# bl_dora2.net
KiCad netlist of a schematic drawn in EAGLE
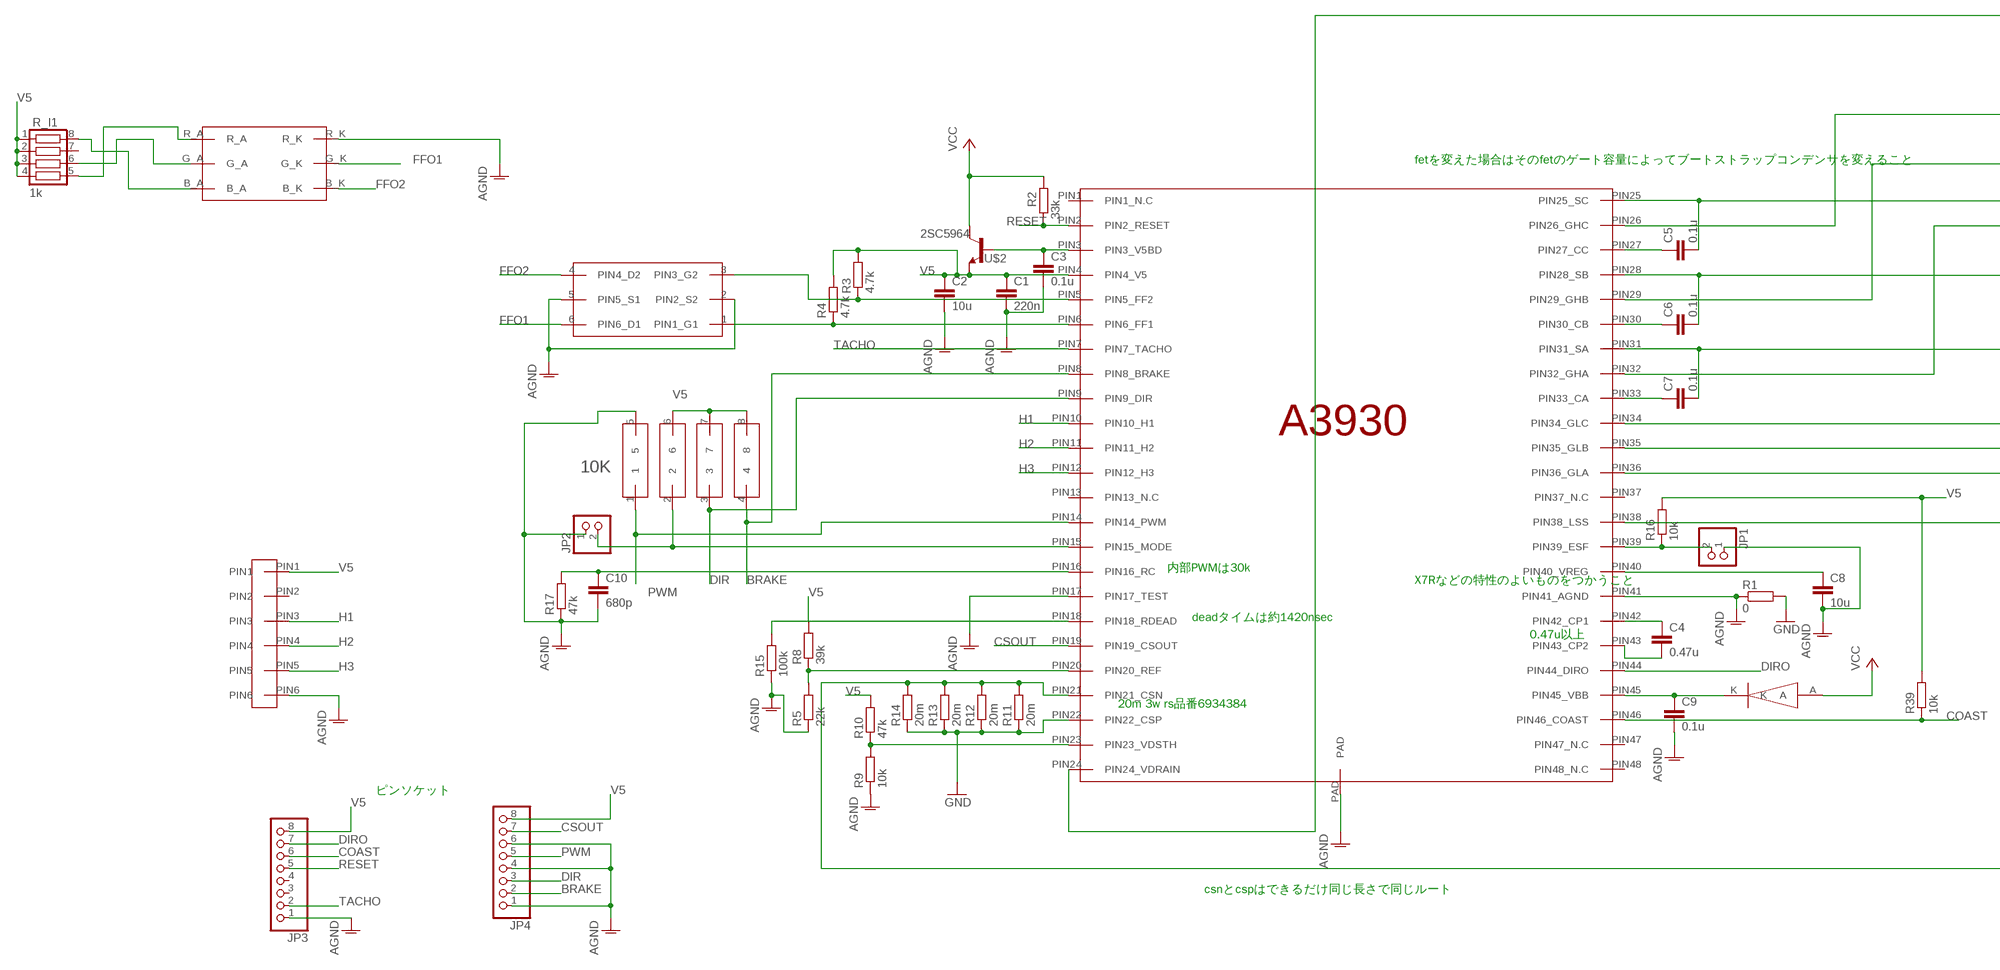
[diagram p0: schematic, sheet 1, part 1 of 2]
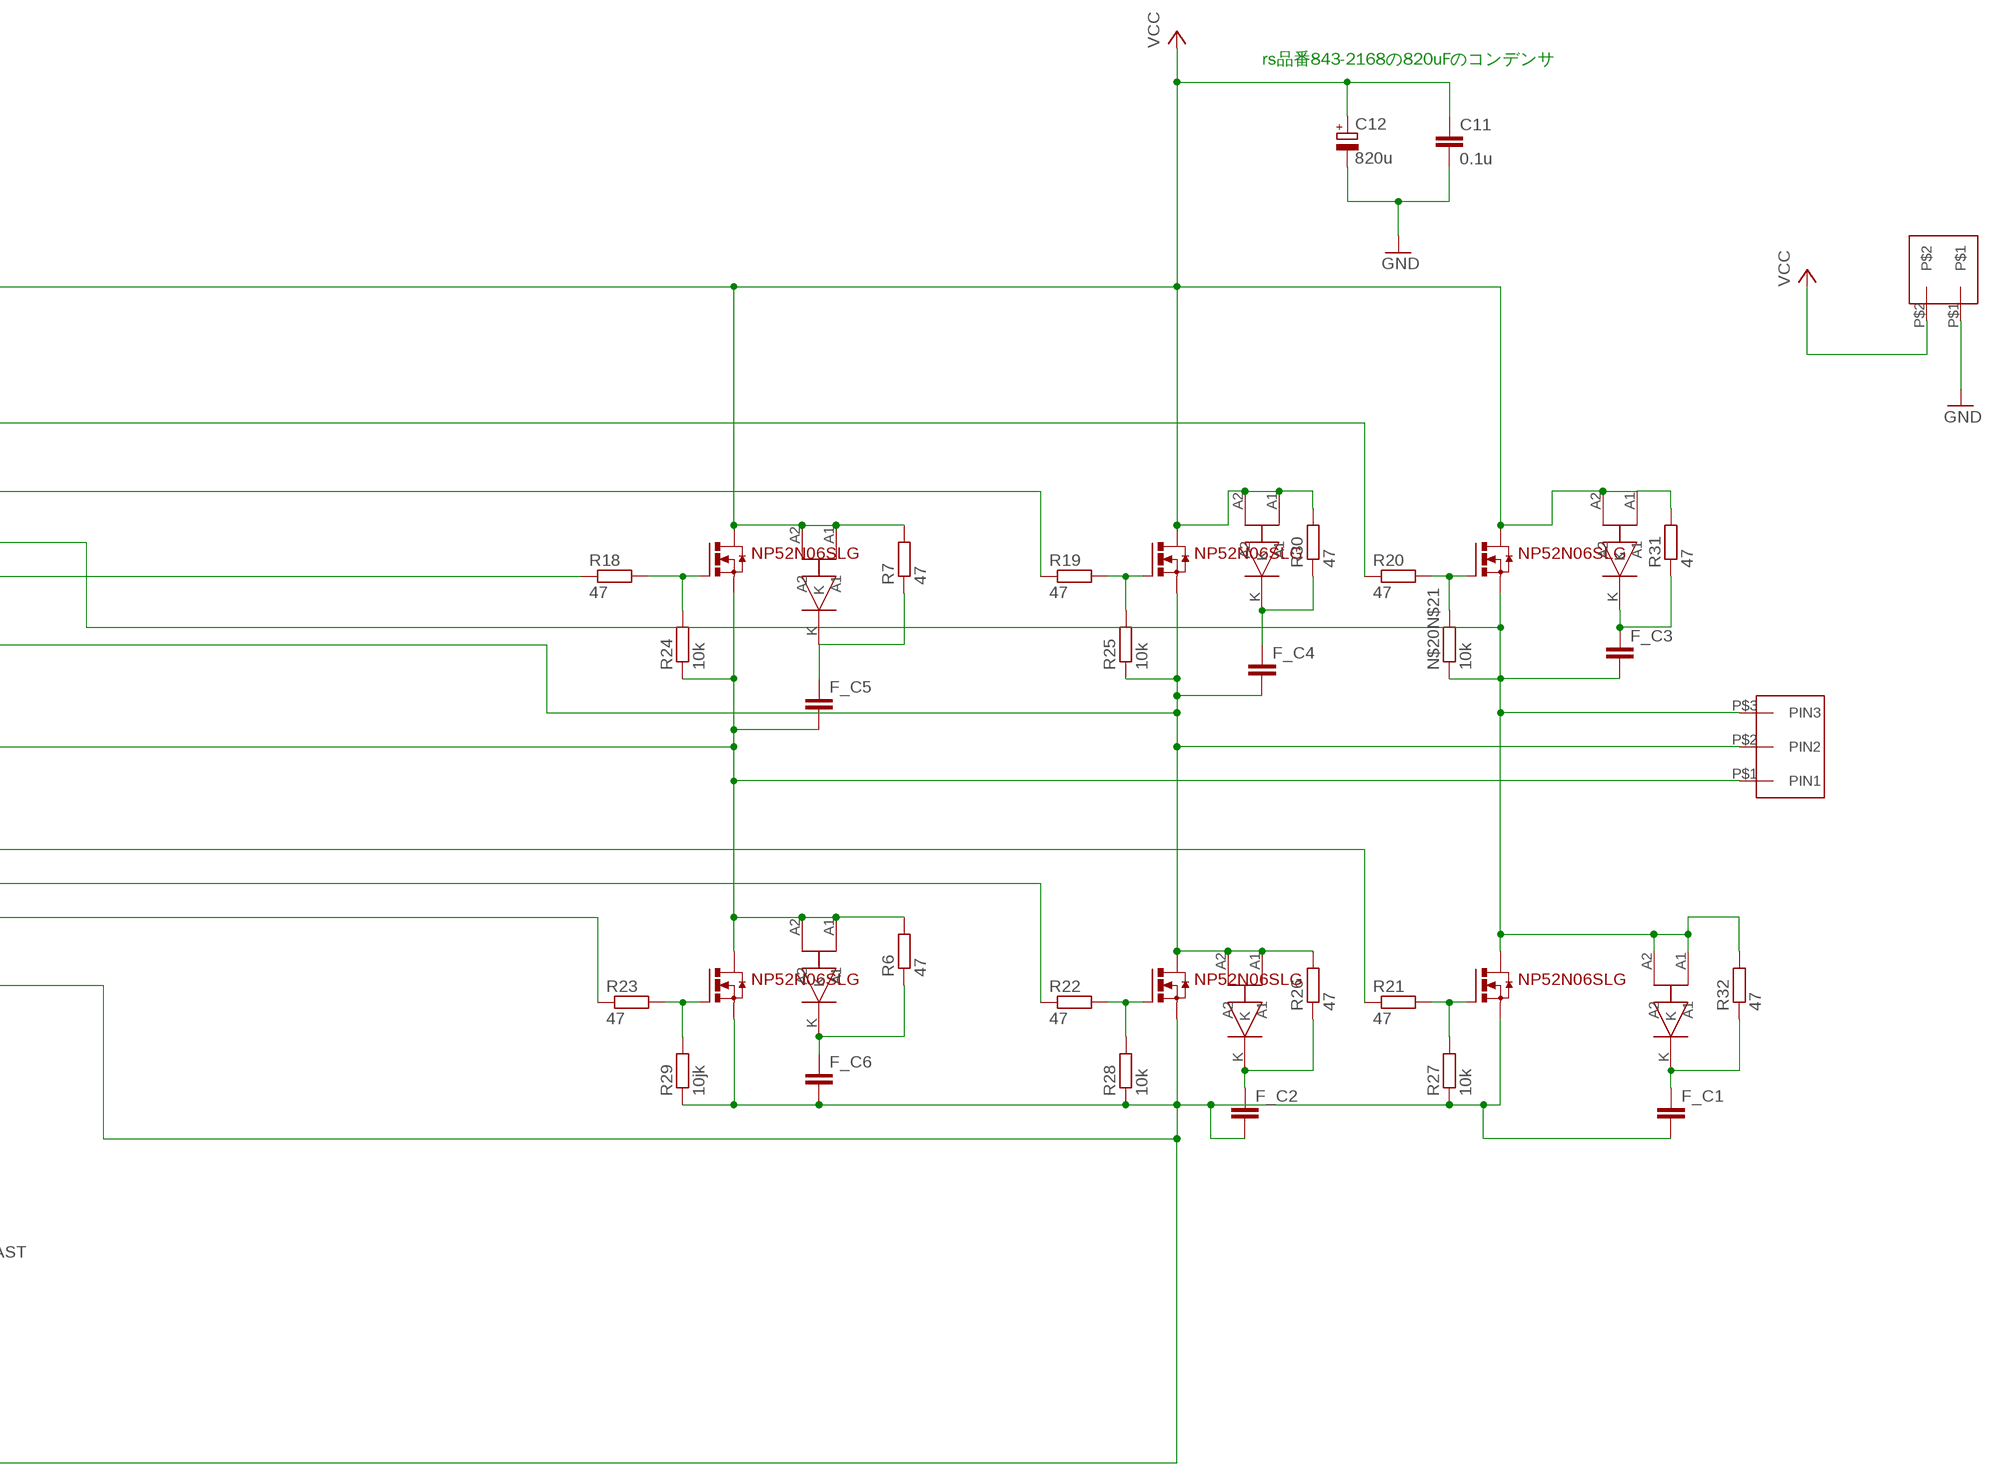
[diagram p1: schematic, sheet 1, part 2 of 2]

(export (version "E")
  (design (tool "Eeschema 10.0.6"))
  (components
    (comp (ref "C1")
      (value "220n")
      (footprint "eagle-import:C2012")
      (libsource (lib "eagle-import") (part "C-EUC2012"))
    )
    (comp (ref "C2")
      (value "10u")
      (footprint "eagle-import:C2012")
      (libsource (lib "eagle-import") (part "C-EUC2012"))
    )
    (comp (ref "C3")
      (value "0.1u")
      (footprint "eagle-import:C2012")
      (libsource (lib "eagle-import") (part "C-EUC2012"))
    )
    (comp (ref "C4")
      (value "0.47u")
      (footprint "eagle-import:C2012")
      (libsource (lib "eagle-import") (part "C-EUC2012"))
    )
    (comp (ref "C5")
      (value "0.1u")
      (footprint "eagle-import:C2012")
      (libsource (lib "eagle-import") (part "C-EUC2012"))
    )
    (comp (ref "C6")
      (value "0.1u")
      (footprint "eagle-import:C2012")
      (libsource (lib "eagle-import") (part "C-EUC2012"))
    )
    (comp (ref "C7")
      (value "0.1u")
      (footprint "eagle-import:C2012")
      (libsource (lib "eagle-import") (part "C-EUC2012"))
    )
    (comp (ref "C8")
      (value "10u")
      (footprint "eagle-import:C2012")
      (libsource (lib "eagle-import") (part "C-EUC2012"))
    )
    (comp (ref "C9")
      (value "0.1u")
      (footprint "eagle-import:C2012")
      (libsource (lib "eagle-import") (part "C-EUC2012"))
    )
    (comp (ref "C10")
      (value "680p")
      (footprint "eagle-import:C2012")
      (libsource (lib "eagle-import") (part "C-EUC2012"))
    )
    (comp (ref "C11")
      (value "0.1u")
      (footprint "eagle-import:C2012")
      (libsource (lib "eagle-import") (part "C-EUC2012"))
    )
    (comp (ref "C12")
      (value "820u")
      (footprint "eagle-import:153CLV-1012")
      (libsource (lib "eagle-import") (part "CPOL-EU153CLV-1012"))
    )
    (comp (ref "F_C1")
      (value "FIL_CAPA")
      (footprint "eagle-import:FIL_CAPA")
      (libsource (lib "eagle-import") (part "FIL_CAPA"))
    )
    (comp (ref "F_C2")
      (value "FIL_CAPA")
      (footprint "eagle-import:FIL_CAPA")
      (libsource (lib "eagle-import") (part "FIL_CAPA"))
    )
    (comp (ref "F_C3")
      (value "FIL_CAPA")
      (footprint "eagle-import:FIL_CAPA")
      (libsource (lib "eagle-import") (part "FIL_CAPA"))
    )
    (comp (ref "F_C4")
      (value "FIL_CAPA")
      (footprint "eagle-import:FIL_CAPA")
      (libsource (lib "eagle-import") (part "FIL_CAPA"))
    )
    (comp (ref "F_C5")
      (value "FIL_CAPA")
      (footprint "eagle-import:FIL_CAPA")
      (libsource (lib "eagle-import") (part "FIL_CAPA"))
    )
    (comp (ref "F_C6")
      (value "FIL_CAPA")
      (footprint "eagle-import:FIL_CAPA")
      (libsource (lib "eagle-import") (part "FIL_CAPA"))
    )
    (comp (ref "JP1")
      (value "PINHD-1X2")
      (footprint "eagle-import:1X02")
      (libsource (lib "eagle-import") (part "PINHD-1X2"))
    )
    (comp (ref "JP2")
      (value "PINHD-1X2")
      (footprint "eagle-import:1X02")
      (libsource (lib "eagle-import") (part "PINHD-1X2"))
    )
    (comp (ref "JP3")
      (value "PINHD-1X8")
      (footprint "eagle-import:1X08")
      (libsource (lib "eagle-import") (part "PINHD-1X8"))
    )
    (comp (ref "JP4")
      (value "PINHD-1X8")
      (footprint "eagle-import:1X08")
      (libsource (lib "eagle-import") (part "PINHD-1X8"))
    )
    (comp (ref "N$20N$21")
      (value "10k")
      (footprint "eagle-import:M2012")
      (libsource (lib "eagle-import") (part "R-EU_M2012"))
    )
    (comp (ref "R1")
      (value "0")
      (footprint "eagle-import:M2012")
      (libsource (lib "eagle-import") (part "R-EU_M2012"))
    )
    (comp (ref "R2")
      (value "33k")
      (footprint "eagle-import:M2012")
      (libsource (lib "eagle-import") (part "R-EU_M2012"))
    )
    (comp (ref "R3")
      (value "4.7k")
      (footprint "eagle-import:M2012")
      (libsource (lib "eagle-import") (part "R-EU_M2012"))
    )
    (comp (ref "R4")
      (value "4.7k")
      (footprint "eagle-import:M2012")
      (libsource (lib "eagle-import") (part "R-EU_M2012"))
    )
    (comp (ref "R5")
      (value "22k")
      (footprint "eagle-import:M2012")
      (libsource (lib "eagle-import") (part "R-EU_M2012"))
    )
    (comp (ref "R6")
      (value "47")
      (footprint "eagle-import:R2512")
      (libsource (lib "eagle-import") (part "R-EU_R2512"))
    )
    (comp (ref "R7")
      (value "47")
      (footprint "eagle-import:R2512")
      (libsource (lib "eagle-import") (part "R-EU_R2512"))
    )
    (comp (ref "R8")
      (value "39k")
      (footprint "eagle-import:M2012")
      (libsource (lib "eagle-import") (part "R-EU_M2012"))
    )
    (comp (ref "R9")
      (value "10k")
      (footprint "eagle-import:M2012")
      (libsource (lib "eagle-import") (part "R-EU_M2012"))
    )
    (comp (ref "R10")
      (value "47k")
      (footprint "eagle-import:M2012")
      (libsource (lib "eagle-import") (part "R-EU_M2012"))
    )
    (comp (ref "R11")
      (value "20m")
      (footprint "eagle-import:R2512")
      (libsource (lib "eagle-import") (part "R-EU_R2512"))
    )
    (comp (ref "R12")
      (value "20m")
      (footprint "eagle-import:R2512")
      (libsource (lib "eagle-import") (part "R-EU_R2512"))
    )
    (comp (ref "R13")
      (value "20m")
      (footprint "eagle-import:R2512")
      (libsource (lib "eagle-import") (part "R-EU_R2512"))
    )
    (comp (ref "R14")
      (value "20m")
      (footprint "eagle-import:R2512")
      (libsource (lib "eagle-import") (part "R-EU_R2512"))
    )
    (comp (ref "R15")
      (value "100k")
      (footprint "eagle-import:M2012")
      (libsource (lib "eagle-import") (part "R-EU_M2012"))
    )
    (comp (ref "R16")
      (value "10k")
      (footprint "eagle-import:M2012")
      (libsource (lib "eagle-import") (part "R-EU_M2012"))
    )
    (comp (ref "R17")
      (value "47k")
      (footprint "eagle-import:M2012")
      (libsource (lib "eagle-import") (part "R-EU_M2012"))
    )
    (comp (ref "R18")
      (value "47")
      (footprint "eagle-import:M2012")
      (libsource (lib "eagle-import") (part "R-EU_M2012"))
    )
    (comp (ref "R19")
      (value "47")
      (footprint "eagle-import:M2012")
      (libsource (lib "eagle-import") (part "R-EU_M2012"))
    )
    (comp (ref "R20")
      (value "47")
      (footprint "eagle-import:M2012")
      (libsource (lib "eagle-import") (part "R-EU_M2012"))
    )
    (comp (ref "R21")
      (value "47")
      (footprint "eagle-import:M2012")
      (libsource (lib "eagle-import") (part "R-EU_M2012"))
    )
    (comp (ref "R22")
      (value "47")
      (footprint "eagle-import:M2012")
      (libsource (lib "eagle-import") (part "R-EU_M2012"))
    )
    (comp (ref "R23")
      (value "47")
      (footprint "eagle-import:M2012")
      (libsource (lib "eagle-import") (part "R-EU_M2012"))
    )
    (comp (ref "R24")
      (value "10k")
      (footprint "eagle-import:M2012")
      (libsource (lib "eagle-import") (part "R-EU_M2012"))
    )
    (comp (ref "R25")
      (value "10k")
      (footprint "eagle-import:M2012")
      (libsource (lib "eagle-import") (part "R-EU_M2012"))
    )
    (comp (ref "R26")
      (value "47")
      (footprint "eagle-import:R2512")
      (libsource (lib "eagle-import") (part "R-EU_R2512"))
    )
    (comp (ref "R27")
      (value "10k")
      (footprint "eagle-import:M2012")
      (libsource (lib "eagle-import") (part "R-EU_M2012"))
    )
    (comp (ref "R28")
      (value "10k")
      (footprint "eagle-import:M2012")
      (libsource (lib "eagle-import") (part "R-EU_M2012"))
    )
    (comp (ref "R29")
      (value "10jk")
      (footprint "eagle-import:M2012")
      (libsource (lib "eagle-import") (part "R-EU_M2012"))
    )
    (comp (ref "R30")
      (value "47")
      (footprint "eagle-import:R2512")
      (libsource (lib "eagle-import") (part "R-EU_R2512"))
    )
    (comp (ref "R31")
      (value "47")
      (footprint "eagle-import:R2512")
      (libsource (lib "eagle-import") (part "R-EU_R2512"))
    )
    (comp (ref "R32")
      (value "47")
      (footprint "eagle-import:R2512")
      (libsource (lib "eagle-import") (part "R-EU_R2512"))
    )
    (comp (ref "R39")
      (value "10k")
      (footprint "eagle-import:M2012")
      (libsource (lib "eagle-import") (part "R-EU_M2012"))
    )
    (comp (ref "R_I1")
      (value "1k")
      (footprint "eagle-import:0603X4RESISTOR")
      (libsource (lib "eagle-import") (part "0603X4RESISTOR"))
    )
    (comp (ref "U$1")
      (value "A3930")
      (footprint "eagle-import:A3930")
      (libsource (lib "eagle-import") (part "A3930"))
    )
    (comp (ref "U$2")
      (value "2SC5964")
      (footprint "eagle-import:2SC5964")
      (libsource (lib "eagle-import") (part "2SC5964"))
    )
    (comp (ref "U$3")
      (value "SSOT6_FET")
      (footprint "eagle-import:SSOT6_FET")
      (libsource (lib "eagle-import") (part "SSOT6_FET"))
    )
    (comp (ref "U$4")
      (value "RGB_LED")
      (footprint "eagle-import:RGB_LED")
      (libsource (lib "eagle-import") (part "RGB_LED"))
    )
    (comp (ref "U$5")
      (value "10K")
      (footprint "eagle-import:1005X4RESISTOR")
      (libsource (lib "eagle-import") (part "1005X4RESISTOR"))
    )
    (comp (ref "U$6")
      (value "SMD_DAIOD")
      (footprint "eagle-import:SMD_DAIOD")
      (libsource (lib "eagle-import") (part "SMD_DAIOD"))
    )
    (comp (ref "U$7")
      (value "NP52N06SLG")
      (footprint "eagle-import:NP52N06SLG")
      (libsource (lib "eagle-import") (part "NP52N06SLG"))
    )
    (comp (ref "U$8")
      (value "NP52N06SLG")
      (footprint "eagle-import:NP52N06SLG")
      (libsource (lib "eagle-import") (part "NP52N06SLG"))
    )
    (comp (ref "U$9")
      (value "NP52N06SLG")
      (footprint "eagle-import:NP52N06SLG")
      (libsource (lib "eagle-import") (part "NP52N06SLG"))
    )
    (comp (ref "U$10")
      (value "NP52N06SLG")
      (footprint "eagle-import:NP52N06SLG")
      (libsource (lib "eagle-import") (part "NP52N06SLG"))
    )
    (comp (ref "U$11")
      (value "NP52N06SLG")
      (footprint "eagle-import:NP52N06SLG")
      (libsource (lib "eagle-import") (part "NP52N06SLG"))
    )
    (comp (ref "U$12")
      (value "NP52N06SLG")
      (footprint "eagle-import:NP52N06SLG")
      (libsource (lib "eagle-import") (part "NP52N06SLG"))
    )
    (comp (ref "U$13")
      (value "SBR10M100P5Q")
      (footprint "eagle-import:SBR10M100P5Q")
      (libsource (lib "eagle-import") (part "SBR10M100P5Q"))
    )
    (comp (ref "U$14")
      (value "SBR10M100P5Q")
      (footprint "eagle-import:SBR10M100P5Q")
      (libsource (lib "eagle-import") (part "SBR10M100P5Q"))
    )
    (comp (ref "U$15")
      (value "SBR10M100P5Q")
      (footprint "eagle-import:SBR10M100P5Q")
      (libsource (lib "eagle-import") (part "SBR10M100P5Q"))
    )
    (comp (ref "U$16")
      (value "SBR10M100P5Q")
      (footprint "eagle-import:SBR10M100P5Q")
      (libsource (lib "eagle-import") (part "SBR10M100P5Q"))
    )
    (comp (ref "U$17")
      (value "SBR10M100P5Q")
      (footprint "eagle-import:SBR10M100P5Q")
      (libsource (lib "eagle-import") (part "SBR10M100P5Q"))
    )
    (comp (ref "U$18")
      (value "SBR10M100P5Q")
      (footprint "eagle-import:SBR10M100P5Q")
      (libsource (lib "eagle-import") (part "SBR10M100P5Q"))
    )
    (comp (ref "U$23")
      (value "ZH_6P")
      (footprint "eagle-import:ZH_6P")
      (libsource (lib "eagle-import") (part "ZH_6P"))
    )
    (comp (ref "U$24")
      (value "XT60")
      (footprint "eagle-import:XT60")
      (libsource (lib "eagle-import") (part "XT60"))
    )
    (comp (ref "U$25")
      (value "VL_3P")
      (footprint "eagle-import:VL_3P")
      (libsource (lib "eagle-import") (part "VL_3P"))
    )
  )
  (nets
    (net (code "1") (name "/BRAKE") (class "Default")
      (node (ref "JP4") (pin "2") (pinfunction "2_2") (pintype "passive"))
      (node (ref "U$1") (pin "PIN8") (pinfunction "PIN8_BRAKE_PIN8") (pintype "bidirectional"))
      (node (ref "U$5") (pin "4") (pinfunction "4_4") (pintype "bidirectional"))
    )
    (net (code "2") (name "/COAST") (class "Default")
      (node (ref "JP3") (pin "6") (pinfunction "6_6") (pintype "passive"))
      (node (ref "R39") (pin "1") (pinfunction "1_1") (pintype "passive"))
      (node (ref "U$1") (pin "PIN46") (pinfunction "PIN46_COAST_PIN46") (pintype "bidirectional"))
    )
    (net (code "3") (name "/CSOUT") (class "Default")
      (node (ref "JP4") (pin "7") (pinfunction "7_7") (pintype "passive"))
      (node (ref "U$1") (pin "PIN19") (pinfunction "PIN19_CSOUT_PIN19") (pintype "bidirectional"))
    )
    (net (code "4") (name "/DIR") (class "Default")
      (node (ref "JP4") (pin "3") (pinfunction "3_3") (pintype "passive"))
      (node (ref "U$1") (pin "PIN9") (pinfunction "PIN9_DIR_PIN9") (pintype "bidirectional"))
      (node (ref "U$5") (pin "3") (pinfunction "3_3") (pintype "bidirectional"))
    )
    (net (code "5") (name "/DIRO") (class "Default")
      (node (ref "JP3") (pin "7") (pinfunction "7_7") (pintype "passive"))
      (node (ref "U$1") (pin "PIN44") (pinfunction "PIN44_DIRO_PIN44") (pintype "bidirectional"))
    )
    (net (code "6") (name "/FFO1") (class "Default")
      (node (ref "U$3") (pin "6") (pinfunction "PIN6_D1_6") (pintype "bidirectional"))
      (node (ref "U$4") (pin "G_K") (pinfunction "G_K_G_K") (pintype "bidirectional"))
    )
    (net (code "7") (name "/FFO2") (class "Default")
      (node (ref "U$3") (pin "4") (pinfunction "PIN4_D2_4") (pintype "bidirectional"))
      (node (ref "U$4") (pin "B_K") (pinfunction "B_K_B_K") (pintype "bidirectional"))
    )
    (net (code "8") (name "/H1") (class "Default")
      (node (ref "U$1") (pin "PIN10") (pinfunction "PIN10_H1_PIN10") (pintype "bidirectional"))
      (node (ref "U$23") (pin "PIN3") (pinfunction "PIN3_PIN3") (pintype "bidirectional"))
    )
    (net (code "9") (name "/H2") (class "Default")
      (node (ref "U$1") (pin "PIN11") (pinfunction "PIN11_H2_PIN11") (pintype "bidirectional"))
      (node (ref "U$23") (pin "PIN4") (pinfunction "PIN4_PIN4") (pintype "bidirectional"))
    )
    (net (code "10") (name "/H3") (class "Default")
      (node (ref "U$1") (pin "PIN12") (pinfunction "PIN12_H3_PIN12") (pintype "bidirectional"))
      (node (ref "U$23") (pin "PIN5") (pinfunction "PIN5_PIN5") (pintype "bidirectional"))
    )
    (net (code "11") (name "/PWM") (class "Default")
      (node (ref "JP4") (pin "5") (pinfunction "5_5") (pintype "passive"))
      (node (ref "U$1") (pin "PIN14") (pinfunction "PIN14_PWM_PIN14") (pintype "bidirectional"))
      (node (ref "U$5") (pin "1") (pinfunction "1_1") (pintype "bidirectional"))
    )
    (net (code "12") (name "/RESET") (class "Default")
      (node (ref "JP3") (pin "5") (pinfunction "5_5") (pintype "passive"))
      (node (ref "R2") (pin "1") (pinfunction "1_1") (pintype "passive"))
      (node (ref "U$1") (pin "PIN2") (pinfunction "PIN2_RESET_PIN2") (pintype "bidirectional"))
    )
    (net (code "13") (name "/TACHO") (class "Default")
      (node (ref "JP3") (pin "2") (pinfunction "2_2") (pintype "passive"))
      (node (ref "U$1") (pin "PIN7") (pinfunction "PIN7_TACHO_PIN7") (pintype "bidirectional"))
    )
    (net (code "14") (name "/V5") (class "Default")
      (node (ref "C1") (pin "1") (pinfunction "1_1") (pintype "passive"))
      (node (ref "C2") (pin "1") (pinfunction "1_1") (pintype "passive"))
      (node (ref "JP3") (pin "8") (pinfunction "8_8") (pintype "passive"))
      (node (ref "JP4") (pin "8") (pinfunction "8_8") (pintype "passive"))
      (node (ref "R10") (pin "2") (pinfunction "2_2") (pintype "passive"))
      (node (ref "R16") (pin "2") (pinfunction "2_2") (pintype "passive"))
      (node (ref "R3") (pin "2") (pinfunction "2_2") (pintype "passive"))
      (node (ref "R39") (pin "2") (pinfunction "2_2") (pintype "passive"))
      (node (ref "R4") (pin "2") (pinfunction "2_2") (pintype "passive"))
      (node (ref "R8") (pin "2") (pinfunction "2_2") (pintype "passive"))
      (node (ref "R_I1") (pin "1") (pinfunction "1_1") (pintype "passive"))
      (node (ref "R_I1") (pin "2") (pinfunction "2_2") (pintype "passive"))
      (node (ref "R_I1") (pin "3") (pinfunction "3_3") (pintype "passive"))
      (node (ref "R_I1") (pin "4") (pinfunction "4_4") (pintype "passive"))
      (node (ref "U$1") (pin "PIN4") (pinfunction "PIN4_V5_PIN4") (pintype "bidirectional"))
      (node (ref "U$2") (pin "E") (pinfunction "E_E") (pintype "passive"))
      (node (ref "U$23") (pin "PIN1") (pinfunction "PIN1_PIN1") (pintype "bidirectional"))
      (node (ref "U$5") (pin "6") (pinfunction "6_6") (pintype "bidirectional"))
      (node (ref "U$5") (pin "7") (pinfunction "7_7") (pintype "bidirectional"))
      (node (ref "U$5") (pin "8") (pinfunction "8_8") (pintype "bidirectional"))
    )
    (net (code "15") (name "AGND") (class "Default")
      (node (ref "C1") (pin "2") (pinfunction "2_2") (pintype "passive"))
      (node (ref "C10") (pin "2") (pinfunction "2_2") (pintype "passive"))
      (node (ref "C2") (pin "2") (pinfunction "2_2") (pintype "passive"))
      (node (ref "C3") (pin "2") (pinfunction "2_2") (pintype "passive"))
      (node (ref "C8") (pin "2") (pinfunction "2_2") (pintype "passive"))
      (node (ref "C9") (pin "2") (pinfunction "2_2") (pintype "passive"))
      (node (ref "JP1") (pin "1") (pinfunction "1_1") (pintype "passive"))
      (node (ref "JP2") (pin "1") (pinfunction "1_1") (pintype "passive"))
      (node (ref "JP3") (pin "1") (pinfunction "1_1") (pintype "passive"))
      (node (ref "JP4") (pin "1") (pinfunction "1_1") (pintype "passive"))
      (node (ref "JP4") (pin "4") (pinfunction "4_4") (pintype "passive"))
      (node (ref "JP4") (pin "6") (pinfunction "6_6") (pintype "passive"))
      (node (ref "R1") (pin "1") (pinfunction "1_1") (pintype "passive"))
      (node (ref "R15") (pin "1") (pinfunction "1_1") (pintype "passive"))
      (node (ref "R17") (pin "1") (pinfunction "1_1") (pintype "passive"))
      (node (ref "R5") (pin "1") (pinfunction "1_1") (pintype "passive"))
      (node (ref "R9") (pin "1") (pinfunction "1_1") (pintype "passive"))
      (node (ref "U$1") (pin "PAD") (pinfunction "PAD_PAD") (pintype "bidirectional"))
      (node (ref "U$1") (pin "PIN17") (pinfunction "PIN17_TEST_PIN17") (pintype "bidirectional"))
      (node (ref "U$1") (pin "PIN41") (pinfunction "PIN41_AGND_PIN41") (pintype "bidirectional"))
      (node (ref "U$23") (pin "PIN6") (pinfunction "PIN6_PIN6") (pintype "bidirectional"))
      (node (ref "U$3") (pin "2") (pinfunction "PIN2_S2_2") (pintype "bidirectional"))
      (node (ref "U$3") (pin "5") (pinfunction "PIN5_S1_5") (pintype "bidirectional"))
      (node (ref "U$4") (pin "R_K") (pinfunction "R_K_R_K") (pintype "bidirectional"))
      (node (ref "U$5") (pin "5") (pinfunction "5_5") (pintype "bidirectional"))
    )
    (net (code "16") (name "GND") (class "Default")
      (node (ref "C11") (pin "2") (pinfunction "2_2") (pintype "passive"))
      (node (ref "C12") (pin "-") (pinfunction "-_-") (pintype "passive"))
      (node (ref "R1") (pin "2") (pinfunction "2_2") (pintype "passive"))
      (node (ref "R11") (pin "1") (pinfunction "1_1") (pintype "passive"))
      (node (ref "R12") (pin "1") (pinfunction "1_1") (pintype "passive"))
      (node (ref "R13") (pin "1") (pinfunction "1_1") (pintype "passive"))
      (node (ref "R14") (pin "1") (pinfunction "1_1") (pintype "passive"))
      (node (ref "U$1") (pin "PIN22") (pinfunction "PIN22_CSP_PIN22") (pintype "bidirectional"))
      (node (ref "U$24") (pin "P$1") (pinfunction "P$1_P$1") (pintype "bidirectional"))
    )
    (net (code "17") (name "Net-(F_C1-1)") (class "Default")
      (node (ref "F_C1") (pin "P$1") (pinfunction "1_P$1") (pintype "passive"))
      (node (ref "R32") (pin "1") (pinfunction "1_1") (pintype "passive"))
      (node (ref "U$18") (pin "K") (pinfunction "K_K") (pintype "bidirectional"))
    )
    (net (code "18") (name "Net-(F_C1-2)") (class "Default")
      (node (ref "F_C1") (pin "P$2") (pinfunction "2_P$2") (pintype "passive"))
      (node (ref "F_C2") (pin "P$2") (pinfunction "2_P$2") (pintype "passive"))
      (node (ref "F_C6") (pin "P$2") (pinfunction "2_P$2") (pintype "passive"))
      (node (ref "R11") (pin "2") (pinfunction "2_2") (pintype "passive"))
      (node (ref "R12") (pin "2") (pinfunction "2_2") (pintype "passive"))
      (node (ref "R13") (pin "2") (pinfunction "2_2") (pintype "passive"))
      (node (ref "R14") (pin "2") (pinfunction "2_2") (pintype "passive"))
      (node (ref "R27") (pin "1") (pinfunction "1_1") (pintype "passive"))
      (node (ref "R28") (pin "1") (pinfunction "1_1") (pintype "passive"))
      (node (ref "R29") (pin "1") (pinfunction "1_1") (pintype "passive"))
      (node (ref "U$1") (pin "PIN21") (pinfunction "PIN21_CSN_PIN21") (pintype "bidirectional"))
      (node (ref "U$1") (pin "PIN38") (pinfunction "PIN38_LSS_PIN38") (pintype "bidirectional"))
      (node (ref "U$10") (pin "PIN3_S") (pinfunction "PIN3_S_PIN3_S") (pintype "passive"))
      (node (ref "U$12") (pin "PIN3_S") (pinfunction "PIN3_S_PIN3_S") (pintype "passive"))
      (node (ref "U$8") (pin "PIN3_S") (pinfunction "PIN3_S_PIN3_S") (pintype "passive"))
    )
    (net (code "19") (name "Net-(F_C2-1)") (class "Default")
      (node (ref "F_C2") (pin "P$1") (pinfunction "1_P$1") (pintype "passive"))
      (node (ref "R26") (pin "1") (pinfunction "1_1") (pintype "passive"))
      (node (ref "U$15") (pin "K") (pinfunction "K_K") (pintype "bidirectional"))
    )
    (net (code "20") (name "Net-(F_C3-1)") (class "Default")
      (node (ref "F_C3") (pin "P$1") (pinfunction "1_P$1") (pintype "passive"))
      (node (ref "R31") (pin "1") (pinfunction "1_1") (pintype "passive"))
      (node (ref "U$17") (pin "K") (pinfunction "K_K") (pintype "bidirectional"))
    )
    (net (code "21") (name "Net-(F_C3-2)") (class "Default")
      (node (ref "C5") (pin "2") (pinfunction "2_2") (pintype "passive"))
      (node (ref "F_C3") (pin "P$2") (pinfunction "2_P$2") (pintype "passive"))
      (node (ref "N$20N$21") (pin "1") (pinfunction "1_1") (pintype "passive"))
      (node (ref "R32") (pin "2") (pinfunction "2_2") (pintype "passive"))
      (node (ref "U$1") (pin "PIN25") (pinfunction "PIN25_SC_PIN25") (pintype "bidirectional"))
      (node (ref "U$11") (pin "PIN3_S") (pinfunction "PIN3_S_PIN3_S") (pintype "passive"))
      (node (ref "U$12") (pin "PIN2_D") (pinfunction "PIN2_D_PIN2_D") (pintype "passive"))
      (node (ref "U$18") (pin "A1") (pinfunction "A1_A1") (pintype "bidirectional"))
      (node (ref "U$18") (pin "A2") (pinfunction "A2_A2") (pintype "bidirectional"))
      (node (ref "U$25") (pin "P$3") (pinfunction "PIN3_P$3") (pintype "bidirectional"))
    )
    (net (code "22") (name "Net-(F_C4-1)") (class "Default")
      (node (ref "F_C4") (pin "P$1") (pinfunction "1_P$1") (pintype "passive"))
      (node (ref "R30") (pin "1") (pinfunction "1_1") (pintype "passive"))
      (node (ref "U$16") (pin "K") (pinfunction "K_K") (pintype "bidirectional"))
    )
    (net (code "23") (name "Net-(F_C4-2)") (class "Default")
      (node (ref "C6") (pin "2") (pinfunction "2_2") (pintype "passive"))
      (node (ref "F_C4") (pin "P$2") (pinfunction "2_P$2") (pintype "passive"))
      (node (ref "R25") (pin "1") (pinfunction "1_1") (pintype "passive"))
      (node (ref "R26") (pin "2") (pinfunction "2_2") (pintype "passive"))
      (node (ref "U$1") (pin "PIN28") (pinfunction "PIN28_SB_PIN28") (pintype "bidirectional"))
      (node (ref "U$10") (pin "PIN2_D") (pinfunction "PIN2_D_PIN2_D") (pintype "passive"))
      (node (ref "U$15") (pin "A1") (pinfunction "A1_A1") (pintype "bidirectional"))
      (node (ref "U$15") (pin "A2") (pinfunction "A2_A2") (pintype "bidirectional"))
      (node (ref "U$25") (pin "P$2") (pinfunction "PIN2_P$2") (pintype "bidirectional"))
      (node (ref "U$9") (pin "PIN3_S") (pinfunction "PIN3_S_PIN3_S") (pintype "passive"))
    )
    (net (code "24") (name "Net-(F_C5-1)") (class "Default")
      (node (ref "F_C5") (pin "P$1") (pinfunction "1_P$1") (pintype "passive"))
      (node (ref "R7") (pin "1") (pinfunction "1_1") (pintype "passive"))
      (node (ref "U$13") (pin "K") (pinfunction "K_K") (pintype "bidirectional"))
    )
    (net (code "25") (name "Net-(F_C5-2)") (class "Default")
      (node (ref "C7") (pin "2") (pinfunction "2_2") (pintype "passive"))
      (node (ref "F_C5") (pin "P$2") (pinfunction "2_P$2") (pintype "passive"))
      (node (ref "R24") (pin "1") (pinfunction "1_1") (pintype "passive"))
      (node (ref "R6") (pin "2") (pinfunction "2_2") (pintype "passive"))
      (node (ref "U$1") (pin "PIN31") (pinfunction "PIN31_SA_PIN31") (pintype "bidirectional"))
      (node (ref "U$14") (pin "A1") (pinfunction "A1_A1") (pintype "bidirectional"))
      (node (ref "U$14") (pin "A2") (pinfunction "A2_A2") (pintype "bidirectional"))
      (node (ref "U$25") (pin "P$1") (pinfunction "PIN1_P$1") (pintype "bidirectional"))
      (node (ref "U$7") (pin "PIN3_S") (pinfunction "PIN3_S_PIN3_S") (pintype "passive"))
      (node (ref "U$8") (pin "PIN2_D") (pinfunction "PIN2_D_PIN2_D") (pintype "passive"))
    )
    (net (code "26") (name "Net-(F_C6-1)") (class "Default")
      (node (ref "F_C6") (pin "P$1") (pinfunction "1_P$1") (pintype "passive"))
      (node (ref "R6") (pin "1") (pinfunction "1_1") (pintype "passive"))
      (node (ref "U$14") (pin "K") (pinfunction "K_K") (pintype "bidirectional"))
    )
    (net (code "27") (name "Net-(N$20N$21-Pad2)") (class "Default")
      (node (ref "N$20N$21") (pin "2") (pinfunction "2_2") (pintype "passive"))
      (node (ref "R20") (pin "2") (pinfunction "2_2") (pintype "passive"))
      (node (ref "U$11") (pin "PIN1_G") (pinfunction "PIN1_G_PIN1_G") (pintype "passive"))
    )
    (net (code "28") (name "Net-(R18-Pad2)") (class "Default")
      (node (ref "R18") (pin "2") (pinfunction "2_2") (pintype "passive"))
      (node (ref "R24") (pin "2") (pinfunction "2_2") (pintype "passive"))
      (node (ref "U$7") (pin "PIN1_G") (pinfunction "PIN1_G_PIN1_G") (pintype "passive"))
    )
    (net (code "29") (name "Net-(R19-Pad2)") (class "Default")
      (node (ref "R19") (pin "2") (pinfunction "2_2") (pintype "passive"))
      (node (ref "R25") (pin "2") (pinfunction "2_2") (pintype "passive"))
      (node (ref "U$9") (pin "PIN1_G") (pinfunction "PIN1_G_PIN1_G") (pintype "passive"))
    )
    (net (code "30") (name "Net-(R21-Pad2)") (class "Default")
      (node (ref "R21") (pin "2") (pinfunction "2_2") (pintype "passive"))
      (node (ref "R27") (pin "2") (pinfunction "2_2") (pintype "passive"))
      (node (ref "U$12") (pin "PIN1_G") (pinfunction "PIN1_G_PIN1_G") (pintype "passive"))
    )
    (net (code "31") (name "Net-(R22-Pad2)") (class "Default")
      (node (ref "R22") (pin "2") (pinfunction "2_2") (pintype "passive"))
      (node (ref "R28") (pin "2") (pinfunction "2_2") (pintype "passive"))
      (node (ref "U$10") (pin "PIN1_G") (pinfunction "PIN1_G_PIN1_G") (pintype "passive"))
    )
    (net (code "32") (name "Net-(R23-Pad2)") (class "Default")
      (node (ref "R23") (pin "2") (pinfunction "2_2") (pintype "passive"))
      (node (ref "R29") (pin "2") (pinfunction "2_2") (pintype "passive"))
      (node (ref "U$8") (pin "PIN1_G") (pinfunction "PIN1_G_PIN1_G") (pintype "passive"))
    )
    (net (code "33") (name "Net-(R_I1-Pad5)") (class "Default")
      (node (ref "R_I1") (pin "5") (pinfunction "5_5") (pintype "passive"))
      (node (ref "U$4") (pin "R_A") (pinfunction "R_A_R_A") (pintype "bidirectional"))
    )
    (net (code "34") (name "Net-(R_I1-Pad6)") (class "Default")
      (node (ref "R_I1") (pin "6") (pinfunction "6_6") (pintype "passive"))
      (node (ref "U$4") (pin "G_A") (pinfunction "G_A_G_A") (pintype "bidirectional"))
    )
    (net (code "35") (name "Net-(R_I1-Pad8)") (class "Default")
      (node (ref "R_I1") (pin "8") (pinfunction "8_8") (pintype "passive"))
      (node (ref "U$4") (pin "B_A") (pinfunction "B_A_B_A") (pintype "bidirectional"))
    )
    (net (code "36") (name "Net-(U$1-PIN3_V5BD)") (class "Default")
      (node (ref "C3") (pin "1") (pinfunction "1_1") (pintype "passive"))
      (node (ref "U$1") (pin "PIN3") (pinfunction "PIN3_V5BD_PIN3") (pintype "bidirectional"))
      (node (ref "U$2") (pin "B") (pinfunction "B_B") (pintype "passive"))
    )
    (net (code "37") (name "Net-(U$1-PIN5_FF2)") (class "Default")
      (node (ref "R3") (pin "1") (pinfunction "1_1") (pintype "passive"))
      (node (ref "U$1") (pin "PIN5") (pinfunction "PIN5_FF2_PIN5") (pintype "bidirectional"))
      (node (ref "U$3") (pin "3") (pinfunction "PIN3_G2_3") (pintype "bidirectional"))
    )
    (net (code "38") (name "Net-(U$1-PIN6_FF1)") (class "Default")
      (node (ref "R4") (pin "1") (pinfunction "1_1") (pintype "passive"))
      (node (ref "U$1") (pin "PIN6") (pinfunction "PIN6_FF1_PIN6") (pintype "bidirectional"))
      (node (ref "U$3") (pin "1") (pinfunction "PIN1_G1_1") (pintype "bidirectional"))
    )
    (net (code "39") (name "Net-(U$1-PIN15_MODE)") (class "Default")
      (node (ref "JP2") (pin "2") (pinfunction "2_2") (pintype "passive"))
      (node (ref "U$1") (pin "PIN15") (pinfunction "PIN15_MODE_PIN15") (pintype "bidirectional"))
      (node (ref "U$5") (pin "2") (pinfunction "2_2") (pintype "bidirectional"))
    )
    (net (code "40") (name "Net-(U$1-PIN16_RC)") (class "Default")
      (node (ref "C10") (pin "1") (pinfunction "1_1") (pintype "passive"))
      (node (ref "R17") (pin "2") (pinfunction "2_2") (pintype "passive"))
      (node (ref "U$1") (pin "PIN16") (pinfunction "PIN16_RC_PIN16") (pintype "bidirectional"))
    )
    (net (code "41") (name "Net-(U$1-PIN18_RDEAD)") (class "Default")
      (node (ref "R15") (pin "2") (pinfunction "2_2") (pintype "passive"))
      (node (ref "U$1") (pin "PIN18") (pinfunction "PIN18_RDEAD_PIN18") (pintype "bidirectional"))
    )
    (net (code "42") (name "Net-(U$1-PIN20_REF)") (class "Default")
      (node (ref "R5") (pin "2") (pinfunction "2_2") (pintype "passive"))
      (node (ref "R8") (pin "1") (pinfunction "1_1") (pintype "passive"))
      (node (ref "U$1") (pin "PIN20") (pinfunction "PIN20_REF_PIN20") (pintype "bidirectional"))
    )
    (net (code "43") (name "Net-(U$1-PIN23_VDSTH)") (class "Default")
      (node (ref "R10") (pin "1") (pinfunction "1_1") (pintype "passive"))
      (node (ref "R9") (pin "2") (pinfunction "2_2") (pintype "passive"))
      (node (ref "U$1") (pin "PIN23") (pinfunction "PIN23_VDSTH_PIN23") (pintype "bidirectional"))
    )
    (net (code "44") (name "Net-(U$1-PIN26_GHC)") (class "Default")
      (node (ref "R20") (pin "1") (pinfunction "1_1") (pintype "passive"))
      (node (ref "U$1") (pin "PIN26") (pinfunction "PIN26_GHC_PIN26") (pintype "bidirectional"))
    )
    (net (code "45") (name "Net-(U$1-PIN27_CC)") (class "Default")
      (node (ref "C5") (pin "1") (pinfunction "1_1") (pintype "passive"))
      (node (ref "U$1") (pin "PIN27") (pinfunction "PIN27_CC_PIN27") (pintype "bidirectional"))
    )
    (net (code "46") (name "Net-(U$1-PIN29_GHB)") (class "Default")
      (node (ref "R19") (pin "1") (pinfunction "1_1") (pintype "passive"))
      (node (ref "U$1") (pin "PIN29") (pinfunction "PIN29_GHB_PIN29") (pintype "bidirectional"))
    )
    (net (code "47") (name "Net-(U$1-PIN30_CB)") (class "Default")
      (node (ref "C6") (pin "1") (pinfunction "1_1") (pintype "passive"))
      (node (ref "U$1") (pin "PIN30") (pinfunction "PIN30_CB_PIN30") (pintype "bidirectional"))
    )
    (net (code "48") (name "Net-(U$1-PIN32_GHA)") (class "Default")
      (node (ref "R18") (pin "1") (pinfunction "1_1") (pintype "passive"))
      (node (ref "U$1") (pin "PIN32") (pinfunction "PIN32_GHA_PIN32") (pintype "bidirectional"))
    )
    (net (code "49") (name "Net-(U$1-PIN33_CA)") (class "Default")
      (node (ref "C7") (pin "1") (pinfunction "1_1") (pintype "passive"))
      (node (ref "U$1") (pin "PIN33") (pinfunction "PIN33_CA_PIN33") (pintype "bidirectional"))
    )
    (net (code "50") (name "Net-(U$1-PIN34_GLC)") (class "Default")
      (node (ref "R21") (pin "1") (pinfunction "1_1") (pintype "passive"))
      (node (ref "U$1") (pin "PIN34") (pinfunction "PIN34_GLC_PIN34") (pintype "bidirectional"))
    )
    (net (code "51") (name "Net-(U$1-PIN35_GLB)") (class "Default")
      (node (ref "R22") (pin "1") (pinfunction "1_1") (pintype "passive"))
      (node (ref "U$1") (pin "PIN35") (pinfunction "PIN35_GLB_PIN35") (pintype "bidirectional"))
    )
    (net (code "52") (name "Net-(U$1-PIN36_GLA)") (class "Default")
      (node (ref "R23") (pin "1") (pinfunction "1_1") (pintype "passive"))
      (node (ref "U$1") (pin "PIN36") (pinfunction "PIN36_GLA_PIN36") (pintype "bidirectional"))
    )
    (net (code "53") (name "Net-(U$1-PIN39_ESF)") (class "Default")
      (node (ref "JP1") (pin "2") (pinfunction "2_2") (pintype "passive"))
      (node (ref "R16") (pin "1") (pinfunction "1_1") (pintype "passive"))
      (node (ref "U$1") (pin "PIN39") (pinfunction "PIN39_ESF_PIN39") (pintype "bidirectional"))
    )
    (net (code "54") (name "Net-(U$1-PIN40_VREG)") (class "Default")
      (node (ref "C8") (pin "1") (pinfunction "1_1") (pintype "passive"))
      (node (ref "U$1") (pin "PIN40") (pinfunction "PIN40_VREG_PIN40") (pintype "bidirectional"))
    )
    (net (code "55") (name "Net-(U$1-PIN42_CP1)") (class "Default")
      (node (ref "C4") (pin "1") (pinfunction "1_1") (pintype "passive"))
      (node (ref "U$1") (pin "PIN42") (pinfunction "PIN42_CP1_PIN42") (pintype "bidirectional"))
    )
    (net (code "56") (name "Net-(U$1-PIN43_CP2)") (class "Default")
      (node (ref "C4") (pin "2") (pinfunction "2_2") (pintype "passive"))
      (node (ref "U$1") (pin "PIN43") (pinfunction "PIN43_CP2_PIN43") (pintype "bidirectional"))
    )
    (net (code "57") (name "Net-(U$1-PIN45_VBB)") (class "Default")
      (node (ref "C9") (pin "1") (pinfunction "1_1") (pintype "passive"))
      (node (ref "U$1") (pin "PIN45") (pinfunction "PIN45_VBB_PIN45") (pintype "bidirectional"))
      (node (ref "U$6") (pin "K") (pinfunction "K_K") (pintype "bidirectional"))
    )
    (net (code "58") (name "VCC") (class "Default")
      (node (ref "C11") (pin "1") (pinfunction "1_1") (pintype "passive"))
      (node (ref "C12") (pin "+") (pinfunction "+_+") (pintype "passive"))
      (node (ref "R2") (pin "2") (pinfunction "2_2") (pintype "passive"))
      (node (ref "R30") (pin "2") (pinfunction "2_2") (pintype "passive"))
      (node (ref "R31") (pin "2") (pinfunction "2_2") (pintype "passive"))
      (node (ref "R7") (pin "2") (pinfunction "2_2") (pintype "passive"))
      (node (ref "U$1") (pin "PIN24") (pinfunction "PIN24_VDRAIN_PIN24") (pintype "bidirectional"))
      (node (ref "U$11") (pin "PIN2_D") (pinfunction "PIN2_D_PIN2_D") (pintype "passive"))
      (node (ref "U$13") (pin "A1") (pinfunction "A1_A1") (pintype "bidirectional"))
      (node (ref "U$13") (pin "A2") (pinfunction "A2_A2") (pintype "bidirectional"))
      (node (ref "U$16") (pin "A1") (pinfunction "A1_A1") (pintype "bidirectional"))
      (node (ref "U$16") (pin "A2") (pinfunction "A2_A2") (pintype "bidirectional"))
      (node (ref "U$17") (pin "A1") (pinfunction "A1_A1") (pintype "bidirectional"))
      (node (ref "U$17") (pin "A2") (pinfunction "A2_A2") (pintype "bidirectional"))
      (node (ref "U$2") (pin "C") (pinfunction "C_C") (pintype "passive"))
      (node (ref "U$2") (pin "C@2") (pinfunction "C_C@2") (pintype "passive"))
      (node (ref "U$24") (pin "P$2") (pinfunction "P$2_P$2") (pintype "bidirectional"))
      (node (ref "U$6") (pin "A") (pinfunction "A_A") (pintype "bidirectional"))
      (node (ref "U$7") (pin "PIN2_D") (pinfunction "PIN2_D_PIN2_D") (pintype "passive"))
      (node (ref "U$9") (pin "PIN2_D") (pinfunction "PIN2_D_PIN2_D") (pintype "passive"))
    )
    (net (code "59") (name "unconnected-(JP3-Pad3)") (class "Default")
      (node (ref "JP3") (pin "3") (pinfunction "3_3") (pintype "passive"))
    )
    (net (code "60") (name "unconnected-(JP3-Pad4)") (class "Default")
      (node (ref "JP3") (pin "4") (pinfunction "4_4") (pintype "passive"))
    )
    (net (code "61") (name "unconnected-(R_I1-Pad7)") (class "Default")
      (node (ref "R_I1") (pin "7") (pinfunction "7_7") (pintype "passive"))
    )
    (net (code "62") (name "unconnected-(U$1-PIN1_N.C-PadPIN1)") (class "Default")
      (node (ref "U$1") (pin "PIN1") (pinfunction "PIN1_N.C_PIN1") (pintype "bidirectional"))
    )
    (net (code "63") (name "unconnected-(U$1-PIN13_N.C-PadPIN13)") (class "Default")
      (node (ref "U$1") (pin "PIN13") (pinfunction "PIN13_N.C_PIN13") (pintype "bidirectional"))
    )
    (net (code "64") (name "unconnected-(U$1-PIN37_N.C-PadPIN37)") (class "Default")
      (node (ref "U$1") (pin "PIN37") (pinfunction "PIN37_N.C_PIN37") (pintype "bidirectional"))
    )
    (net (code "65") (name "unconnected-(U$1-PIN47_N.C-PadPIN47)") (class "Default")
      (node (ref "U$1") (pin "PIN47") (pinfunction "PIN47_N.C_PIN47") (pintype "bidirectional"))
    )
    (net (code "66") (name "unconnected-(U$1-PIN48_N.C-PadPIN48)") (class "Default")
      (node (ref "U$1") (pin "PIN48") (pinfunction "PIN48_N.C_PIN48") (pintype "bidirectional"))
    )
    (net (code "67") (name "unconnected-(U$23-PadPIN2)") (class "Default")
      (node (ref "U$23") (pin "PIN2") (pinfunction "PIN2_PIN2") (pintype "bidirectional"))
    )
  )
)
